# 03_LCD-Other.net
KiCad netlist of a schematic drawn in Altium Designer
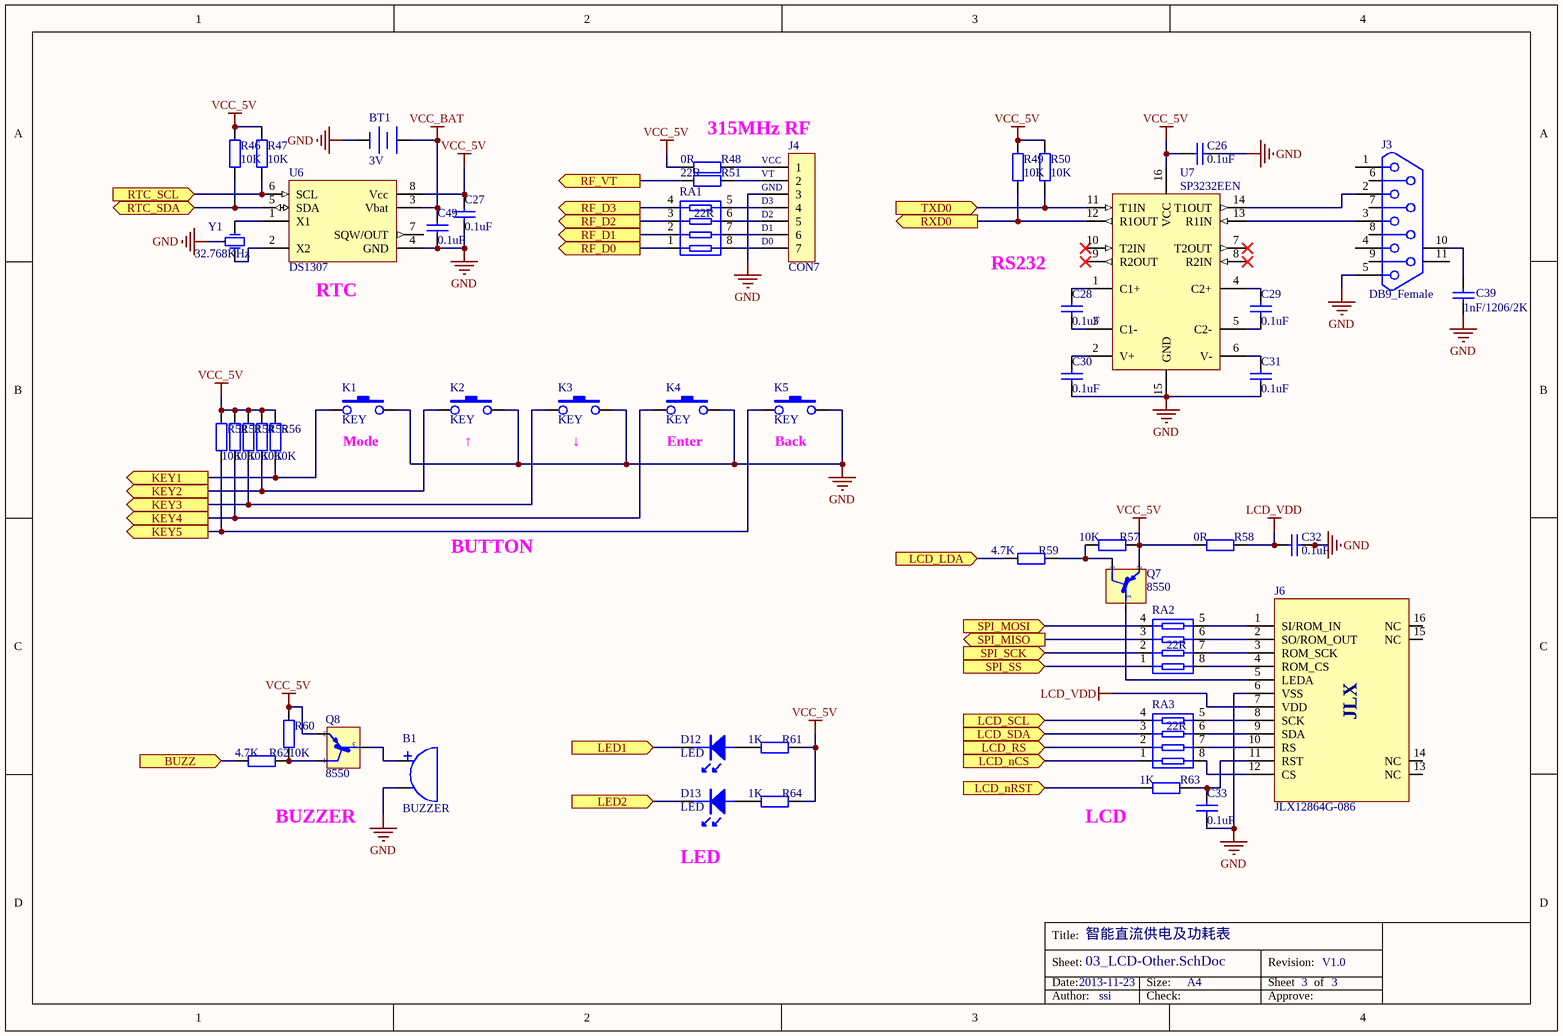
[diagram p0: 03_LCD-Other.SchDoc]

(export (version "E")
  (design (tool "Eeschema 10.0.6"))
  (components
    (comp (ref "B1")
      (value "BUZZER")
      (footprint "BUZZ")
      (description "Buzzer")
      (libsource (lib "SSD-Schlib1") (part "BUZZER"))
    )
    (comp (ref "BT1")
      (value "3V")
      (footprint "BATTERY_Mi")
      (description "Multicell Battery")
      (fields (field (name "PUBLISHER") "Altium Limited"))
      (libsource (lib "SSD-Schlib1") (part "Battery"))
    )
    (comp (ref "C26")
      (value "0.1uF")
      (footprint "0603C")
      (description "Capacitor")
      (fields (field (name "PUBLISHER") "Altium Limited"))
      (libsource (lib "SSD_LibPkg") (part "Cap"))
    )
    (comp (ref "C27")
      (value "0.1uF")
      (footprint "0603C")
      (description "Capacitor")
      (fields (field (name "PUBLISHER") "Altium Limited"))
      (libsource (lib "SSD-Schlib1") (part "Cap"))
    )
    (comp (ref "C28")
      (value "0.1uF")
      (footprint "0603C")
      (description "Capacitor")
      (fields (field (name "PUBLISHER") "Altium Limited"))
      (libsource (lib "SSD-Schlib1") (part "Cap"))
    )
    (comp (ref "C29")
      (value "0.1uF")
      (footprint "0603C")
      (description "Capacitor")
      (fields (field (name "PUBLISHER") "Altium Limited"))
      (libsource (lib "SSD-Schlib1") (part "Cap"))
    )
    (comp (ref "C30")
      (value "0.1uF")
      (footprint "0603C")
      (description "Capacitor")
      (fields (field (name "PUBLISHER") "Altium Limited"))
      (libsource (lib "SSD-Schlib1") (part "Cap"))
    )
    (comp (ref "C31")
      (value "0.1uF")
      (footprint "0603C")
      (description "Capacitor")
      (fields (field (name "PUBLISHER") "Altium Limited"))
      (libsource (lib "SSD-Schlib1") (part "Cap"))
    )
    (comp (ref "C32")
      (value "0.1uF")
      (footprint "0603C")
      (description "Capacitor")
      (fields (field (name "PUBLISHER") "Altium Limited"))
      (libsource (lib "SSD_LibPkg") (part "Cap"))
    )
    (comp (ref "C33")
      (value "0.1uF")
      (footprint "0603C")
      (description "Capacitor")
      (fields (field (name "PUBLISHER") "Altium Limited"))
      (libsource (lib "SSD_LibPkg") (part "Cap"))
    )
    (comp (ref "C39")
      (value "1nF/1206/2K")
      (footprint "1206")
      (description "Capacitor")
      (fields (field (name "PUBLISHER") "Altium Limited"))
      (libsource (lib "SSD-Schlib1") (part "Cap"))
    )
    (comp (ref "C49")
      (value "0.1uF")
      (footprint "0603C")
      (description "Capacitor")
      (fields (field (name "PUBLISHER") "Altium Limited"))
      (libsource (lib "SSD_LibPkg") (part "Cap"))
    )
    (comp (ref "D12") (value "LED") (footprint "LED-3.5mm") (libsource (lib "SSD-Schlib1") (part "LED")))
    (comp (ref "D13") (value "LED") (footprint "LED-3.5mm") (libsource (lib "SSD-Schlib1") (part "LED")))
    (comp (ref "J3")
      (value "DB9_Female")
      (footprint "DB9_F")
      (description "DB9_Female 母")
      (libsource (lib "SSD-Schlib1") (part "DB9_F"))
    )
    (comp (ref "J4") (value "CON7") (footprint "SIP7") (libsource (lib "SSD-Schlib1") (part "CON7")))
    (comp (ref "J6")
      (value "JLX12864G-086")
      (footprint "JLX12864G-086")
      (description "LCD12864 mini,43.5x40.8mm")
      (libsource (lib "SSD_LibPkg") (part "JLX12864G-086"))
    )
    (comp (ref "K1") (value "KEY") (footprint "SW_AJ_6X6") (libsource (lib "SSD-Schlib1") (part "KEY1")))
    (comp (ref "K2") (value "KEY") (footprint "SW_AJ_6X6") (libsource (lib "SSD-Schlib1") (part "KEY1")))
    (comp (ref "K3") (value "KEY") (footprint "SW_AJ_6X6") (libsource (lib "SSD-Schlib1") (part "KEY1")))
    (comp (ref "K4") (value "KEY") (footprint "SW_AJ_6X6") (libsource (lib "SSD-Schlib1") (part "KEY1")))
    (comp (ref "K5") (value "KEY") (footprint "SW_AJ_6X6") (libsource (lib "SSD-Schlib1") (part "KEY1")))
    (comp (ref "Q7")
      (value "8550")
      (footprint "SSD-PCBLIB1:SOT-23")
      (description "PNP")
      (libsource (lib "") (part "PNP_T_1"))
    )
    (comp (ref "Q8")
      (value "8550")
      (footprint "SSD-PCBLIB1:SOT-23")
      (description "PNP")
      (libsource (lib "SSD-Schlib1") (part "PNP_T"))
    )
    (comp (ref "R46")
      (value "10K")
      (footprint "0603")
      (description "Resistor")
      (fields (field (name "PUBLISHER") "Altium Limited"))
      (libsource (lib "SSD_LibPkg") (part "Res2"))
    )
    (comp (ref "R47")
      (value "10K")
      (footprint "0603")
      (description "Resistor")
      (fields (field (name "PUBLISHER") "Altium Limited"))
      (libsource (lib "SSD_LibPkg") (part "Res2"))
    )
    (comp (ref "R48")
      (value "0R")
      (footprint "0603")
      (description "Resistor")
      (fields (field (name "PUBLISHER") "Altium Limited"))
      (libsource (lib "") (part "Res2_1"))
    )
    (comp (ref "R49")
      (value "10K")
      (footprint "0603")
      (description "Resistor")
      (fields (field (name "PUBLISHER") "Altium Limited"))
      (libsource (lib "SSD_LibPkg") (part "Res2"))
    )
    (comp (ref "R50")
      (value "10K")
      (footprint "0603")
      (description "Resistor")
      (fields (field (name "PUBLISHER") "Altium Limited"))
      (libsource (lib "SSD_LibPkg") (part "Res2"))
    )
    (comp (ref "R51")
      (value "22R")
      (footprint "0603")
      (description "Resistor")
      (fields (field (name "PUBLISHER") "Altium Limited"))
      (libsource (lib "") (part "Res2_1"))
    )
    (comp (ref "R52")
      (value "10K")
      (footprint "0603")
      (description "Resistor")
      (fields (field (name "PUBLISHER") "Altium Limited"))
      (libsource (lib "SSD-Schlib1") (part "Res2"))
    )
    (comp (ref "R53")
      (value "10K")
      (footprint "0603")
      (description "Resistor")
      (fields (field (name "PUBLISHER") "Altium Limited"))
      (libsource (lib "SSD-Schlib1") (part "Res2"))
    )
    (comp (ref "R54")
      (value "10K")
      (footprint "0603")
      (description "Resistor")
      (fields (field (name "PUBLISHER") "Altium Limited"))
      (libsource (lib "SSD-Schlib1") (part "Res2"))
    )
    (comp (ref "R55")
      (value "10K")
      (footprint "0603")
      (description "Resistor")
      (fields (field (name "PUBLISHER") "Altium Limited"))
      (libsource (lib "SSD-Schlib1") (part "Res2"))
    )
    (comp (ref "R56")
      (value "10K")
      (footprint "0603")
      (description "Resistor")
      (fields (field (name "PUBLISHER") "Altium Limited"))
      (libsource (lib "SSD-Schlib1") (part "Res2"))
    )
    (comp (ref "R57")
      (value "10K")
      (footprint "0603")
      (description "Resistor")
      (fields (field (name "PUBLISHER") "Altium Limited"))
      (libsource (lib "") (part "Res2_1"))
    )
    (comp (ref "R58")
      (value "0R")
      (footprint "0603")
      (description "Resistor")
      (fields (field (name "PUBLISHER") "Altium Limited"))
      (libsource (lib "") (part "Res2_1"))
    )
    (comp (ref "R59")
      (value "4.7K")
      (footprint "0603")
      (description "Resistor")
      (fields (field (name "PUBLISHER") "Altium Limited"))
      (libsource (lib "") (part "Res2_1"))
    )
    (comp (ref "R60")
      (value "10K")
      (footprint "0603")
      (description "Resistor")
      (fields (field (name "PUBLISHER") "Altium Limited"))
      (libsource (lib "SSD-Schlib1") (part "Res2"))
    )
    (comp (ref "R61")
      (value "1K")
      (footprint "0603")
      (description "Resistor")
      (fields (field (name "PUBLISHER") "Altium Limited"))
      (libsource (lib "") (part "Res2_1"))
    )
    (comp (ref "R62")
      (value "4.7K")
      (footprint "0603")
      (description "Resistor")
      (fields (field (name "PUBLISHER") "Altium Limited"))
      (libsource (lib "") (part "Res2_1"))
    )
    (comp (ref "R63")
      (value "1K")
      (footprint "0603")
      (description "Resistor")
      (fields (field (name "PUBLISHER") "Altium Limited"))
      (libsource (lib "") (part "Res2_1"))
    )
    (comp (ref "R64")
      (value "1K")
      (footprint "0603")
      (description "Resistor")
      (fields (field (name "PUBLISHER") "Altium Limited"))
      (libsource (lib "") (part "Res2_1"))
    )
    (comp (ref "RA1")
      (value "22R")
      (footprint "0603x4")
      (description "Isolated Resistor Network")
      (libsource (lib "SSD_LibPkg") (part "Res x4"))
    )
    (comp (ref "RA2")
      (value "22R")
      (footprint "0603x4")
      (description "Isolated Resistor Network")
      (libsource (lib "SSD_LibPkg") (part "Res x4"))
    )
    (comp (ref "RA3")
      (value "22R")
      (footprint "0603x4")
      (description "Isolated Resistor Network")
      (libsource (lib "SSD_LibPkg") (part "Res x4"))
    )
    (comp (ref "U6") (value "DS1307") (footprint "SO-8") (libsource (lib "SSD-Schlib1") (part "DS1307")))
    (comp (ref "U7")
      (value "SP3232EEN")
      (footprint "SO16")
      (description "3  to 5V Powered, Multi-Channel RS-232 Driver/Receiver")
      (fields (field (name "PUBLISHER") "Altium Limited"))
      (libsource (lib "SSD-Schlib1") (part "SP3232"))
    )
    (comp (ref "Y1")
      (value "32.768KHz")
      (footprint "XTAL-32K-B")
      (description "Crystal Oscillator")
      (fields (field (name "PUBLISHER") "Altium Limited"))
      (libsource (lib "SSD-Schlib1") (part "XTAL32-3"))
    )
  )
  (nets
    (net (code "1") (name "/BUZZ") (class "Default")
      (node (ref "R62") (pin "1") (pinfunction "1_1") (pintype "passive"))
    )
    (net (code "2") (name "/KEY1") (class "Default")
      (node (ref "K1") (pin "1") (pinfunction "1_1") (pintype "passive"))
      (node (ref "R56") (pin "1") (pinfunction "1_1") (pintype "passive"))
    )
    (net (code "3") (name "/KEY2") (class "Default")
      (node (ref "K2") (pin "1") (pinfunction "1_1") (pintype "passive"))
      (node (ref "R55") (pin "1") (pinfunction "1_1") (pintype "passive"))
    )
    (net (code "4") (name "/KEY3") (class "Default")
      (node (ref "K3") (pin "1") (pinfunction "1_1") (pintype "passive"))
      (node (ref "R54") (pin "1") (pinfunction "1_1") (pintype "passive"))
    )
    (net (code "5") (name "/KEY4") (class "Default")
      (node (ref "K4") (pin "1") (pinfunction "1_1") (pintype "passive"))
      (node (ref "R53") (pin "1") (pinfunction "1_1") (pintype "passive"))
    )
    (net (code "6") (name "/KEY5") (class "Default")
      (node (ref "K5") (pin "1") (pinfunction "1_1") (pintype "passive"))
      (node (ref "R52") (pin "1") (pinfunction "1_1") (pintype "passive"))
    )
    (net (code "7") (name "/LCD_LDA") (class "Default")
      (node (ref "R59") (pin "2") (pinfunction "2_2") (pintype "passive"))
    )
    (net (code "8") (name "/LCD_RS") (class "Default")
      (node (ref "RA3") (pin "2") (pinfunction "2_2") (pintype "passive"))
    )
    (net (code "9") (name "/LCD_SCL") (class "Default")
      (node (ref "RA3") (pin "4") (pinfunction "4_4") (pintype "passive"))
    )
    (net (code "10") (name "/LCD_SDA") (class "Default")
      (node (ref "RA3") (pin "3") (pinfunction "3_3") (pintype "passive"))
    )
    (net (code "11") (name "/LCD_nCS") (class "Default")
      (node (ref "RA3") (pin "1") (pinfunction "1_1") (pintype "passive"))
    )
    (net (code "12") (name "/LCD_nRST") (class "Default")
      (node (ref "R63") (pin "2") (pinfunction "2_2") (pintype "passive"))
    )
    (net (code "13") (name "/LED1") (class "Default")
      (node (ref "D12") (pin "2") (pinfunction "K_2") (pintype "passive"))
    )
    (net (code "14") (name "/LED2") (class "Default")
      (node (ref "D13") (pin "2") (pinfunction "K_2") (pintype "passive"))
    )
    (net (code "15") (name "/RF_D0") (class "Default")
      (node (ref "RA1") (pin "1") (pinfunction "1_1") (pintype "passive"))
    )
    (net (code "16") (name "/RF_D1") (class "Default")
      (node (ref "RA1") (pin "2") (pinfunction "2_2") (pintype "passive"))
    )
    (net (code "17") (name "/RF_D2") (class "Default")
      (node (ref "RA1") (pin "3") (pinfunction "3_3") (pintype "passive"))
    )
    (net (code "18") (name "/RF_D3") (class "Default")
      (node (ref "RA1") (pin "4") (pinfunction "4_4") (pintype "passive"))
    )
    (net (code "19") (name "/RF_VT") (class "Default")
      (node (ref "R51") (pin "2") (pinfunction "2_2") (pintype "passive"))
    )
    (net (code "20") (name "/RTC_SCL") (class "Default")
      (node (ref "R47") (pin "2") (pinfunction "2_2") (pintype "passive"))
      (node (ref "U6") (pin "6") (pinfunction "SCL_6") (pintype "input"))
    )
    (net (code "21") (name "/RTC_SDA") (class "Default")
      (node (ref "R46") (pin "2") (pinfunction "2_2") (pintype "passive"))
      (node (ref "U6") (pin "5") (pinfunction "SDA_5") (pintype "bidirectional"))
    )
    (net (code "22") (name "/RXD0") (class "Default")
      (node (ref "R49") (pin "2") (pinfunction "2_2") (pintype "passive"))
      (node (ref "U7") (pin "12") (pinfunction "R1OUT_12") (pintype "output"))
    )
    (net (code "23") (name "/SPI_MISO") (class "Default")
      (node (ref "RA2") (pin "3") (pinfunction "3_3") (pintype "passive"))
    )
    (net (code "24") (name "/SPI_MOSI") (class "Default")
      (node (ref "RA2") (pin "4") (pinfunction "4_4") (pintype "passive"))
    )
    (net (code "25") (name "/SPI_SCK") (class "Default")
      (node (ref "RA2") (pin "2") (pinfunction "2_2") (pintype "passive"))
    )
    (net (code "26") (name "/SPI_SS") (class "Default")
      (node (ref "RA2") (pin "1") (pinfunction "1_1") (pintype "passive"))
    )
    (net (code "27") (name "/TXD0") (class "Default")
      (node (ref "R50") (pin "2") (pinfunction "2_2") (pintype "passive"))
      (node (ref "U7") (pin "11") (pinfunction "T1IN_11") (pintype "input"))
    )
    (net (code "28") (name "GND") (class "Default")
      (node (ref "B1") (pin "2") (pinfunction "B_2") (pintype "passive"))
      (node (ref "BT1") (pin "2") (pinfunction "-_2") (pintype "passive"))
      (node (ref "C26") (pin "1") (pinfunction "1_1") (pintype "passive"))
      (node (ref "C27") (pin "1") (pinfunction "1_1") (pintype "passive"))
      (node (ref "C30") (pin "1") (pinfunction "1_1") (pintype "passive"))
      (node (ref "C31") (pin "1") (pinfunction "1_1") (pintype "passive"))
      (node (ref "C32") (pin "1") (pinfunction "1_1") (pintype "passive"))
      (node (ref "C33") (pin "1") (pinfunction "1_1") (pintype "passive"))
      (node (ref "C39") (pin "1") (pinfunction "1_1") (pintype "passive"))
      (node (ref "C49") (pin "2") (pinfunction "2_2") (pintype "passive"))
      (node (ref "J3") (pin "5") (pinfunction "5_5") (pintype "passive"))
      (node (ref "J4") (pin "3") (pinfunction "3_3") (pintype "passive"))
      (node (ref "J6") (pin "6") (pinfunction "VSS_6") (pintype "passive"))
      (node (ref "K1") (pin "2") (pinfunction "2_2") (pintype "passive"))
      (node (ref "K2") (pin "2") (pinfunction "2_2") (pintype "passive"))
      (node (ref "K3") (pin "2") (pinfunction "2_2") (pintype "passive"))
      (node (ref "K4") (pin "2") (pinfunction "2_2") (pintype "passive"))
      (node (ref "K5") (pin "2") (pinfunction "2_2") (pintype "passive"))
      (node (ref "U6") (pin "4") (pinfunction "GND_4") (pintype "power_in"))
      (node (ref "U7") (pin "15") (pinfunction "GND_15") (pintype "power_in"))
      (node (ref "Y1") (pin "3") (pinfunction "3_3") (pintype "passive"))
    )
    (net (code "29") (name "LCD_VDD") (class "Default")
      (node (ref "C32") (pin "2") (pinfunction "2_2") (pintype "passive"))
      (node (ref "J6") (pin "7") (pinfunction "VDD_7") (pintype "passive"))
      (node (ref "R58") (pin "1") (pinfunction "1_1") (pintype "passive"))
    )
    (net (code "30") (name "Net-(B1-A)") (class "Default")
      (node (ref "B1") (pin "1") (pinfunction "A_1") (pintype "passive"))
      (node (ref "Q8") (pin "3") (pinfunction "C_3") (pintype "passive"))
    )
    (net (code "31") (name "Net-(C39-Pad2)") (class "Default")
      (node (ref "C39") (pin "2") (pinfunction "2_2") (pintype "passive"))
      (node (ref "J3") (pin "10") (pinfunction "10_10") (pintype "passive"))
    )
    (net (code "32") (name "Net-(D12-A)") (class "Default")
      (node (ref "D12") (pin "1") (pinfunction "A_1") (pintype "passive"))
      (node (ref "R61") (pin "1") (pinfunction "1_1") (pintype "passive"))
    )
    (net (code "33") (name "Net-(D13-A)") (class "Default")
      (node (ref "D13") (pin "1") (pinfunction "A_1") (pintype "passive"))
      (node (ref "R64") (pin "1") (pinfunction "1_1") (pintype "passive"))
    )
    (net (code "34") (name "Net-(J4-Pad1)") (class "Default")
      (node (ref "J4") (pin "1") (pinfunction "1_1") (pintype "passive"))
      (node (ref "R48") (pin "1") (pinfunction "1_1") (pintype "passive"))
    )
    (net (code "35") (name "Net-(J4-Pad2)") (class "Default")
      (node (ref "J4") (pin "2") (pinfunction "2_2") (pintype "passive"))
      (node (ref "R51") (pin "1") (pinfunction "1_1") (pintype "passive"))
    )
    (net (code "36") (name "Net-(J4-Pad4)") (class "Default")
      (node (ref "J4") (pin "4") (pinfunction "4_4") (pintype "passive"))
      (node (ref "RA1") (pin "5") (pinfunction "5_5") (pintype "passive"))
    )
    (net (code "37") (name "Net-(J4-Pad5)") (class "Default")
      (node (ref "J4") (pin "5") (pinfunction "5_5") (pintype "passive"))
      (node (ref "RA1") (pin "6") (pinfunction "6_6") (pintype "passive"))
    )
    (net (code "38") (name "Net-(J4-Pad6)") (class "Default")
      (node (ref "J4") (pin "6") (pinfunction "6_6") (pintype "passive"))
      (node (ref "RA1") (pin "7") (pinfunction "7_7") (pintype "passive"))
    )
    (net (code "39") (name "Net-(J4-Pad7)") (class "Default")
      (node (ref "J4") (pin "7") (pinfunction "7_7") (pintype "passive"))
      (node (ref "RA1") (pin "8") (pinfunction "8_8") (pintype "passive"))
    )
    (net (code "40") (name "Net-(J6-CS)") (class "Default")
      (node (ref "J6") (pin "12") (pinfunction "CS_12") (pintype "passive"))
      (node (ref "RA3") (pin "8") (pinfunction "8_8") (pintype "passive"))
    )
    (net (code "41") (name "Net-(J6-LEDA)") (class "Default")
      (node (ref "J6") (pin "5") (pinfunction "LEDA_5") (pintype "passive"))
      (node (ref "Q7") (pin "3") (pinfunction "C_3") (pintype "passive"))
    )
    (net (code "42") (name "Net-(J6-ROM_CS)") (class "Default")
      (node (ref "J6") (pin "4") (pinfunction "ROM_CS_4") (pintype "passive"))
      (node (ref "RA2") (pin "8") (pinfunction "8_8") (pintype "passive"))
    )
    (net (code "43") (name "Net-(J6-ROM_SCK)") (class "Default")
      (node (ref "J6") (pin "3") (pinfunction "ROM_SCK_3") (pintype "passive"))
      (node (ref "RA2") (pin "7") (pinfunction "7_7") (pintype "passive"))
    )
    (net (code "44") (name "Net-(J6-RS)") (class "Default")
      (node (ref "J6") (pin "10") (pinfunction "RS_10") (pintype "passive"))
      (node (ref "RA3") (pin "7") (pinfunction "7_7") (pintype "passive"))
    )
    (net (code "45") (name "Net-(J6-RST)") (class "Default")
      (node (ref "C33") (pin "2") (pinfunction "2_2") (pintype "passive"))
      (node (ref "J6") (pin "11") (pinfunction "RST_11") (pintype "passive"))
      (node (ref "R63") (pin "1") (pinfunction "1_1") (pintype "passive"))
    )
    (net (code "46") (name "Net-(J6-SCK)") (class "Default")
      (node (ref "J6") (pin "8") (pinfunction "SCK_8") (pintype "passive"))
      (node (ref "RA3") (pin "5") (pinfunction "5_5") (pintype "passive"))
    )
    (net (code "47") (name "Net-(J6-SDA)") (class "Default")
      (node (ref "J6") (pin "9") (pinfunction "SDA_9") (pintype "passive"))
      (node (ref "RA3") (pin "6") (pinfunction "6_6") (pintype "passive"))
    )
    (net (code "48") (name "Net-(J6-SI{slash}ROM_IN)") (class "Default")
      (node (ref "J6") (pin "1") (pinfunction "SI/ROM_IN_1") (pintype "passive"))
      (node (ref "RA2") (pin "5") (pinfunction "5_5") (pintype "passive"))
    )
    (net (code "49") (name "Net-(J6-SO{slash}ROM_OUT)") (class "Default")
      (node (ref "J6") (pin "2") (pinfunction "SO/ROM_OUT_2") (pintype "passive"))
      (node (ref "RA2") (pin "6") (pinfunction "6_6") (pintype "passive"))
    )
    (net (code "50") (name "Net-(Q7-B)") (class "Default")
      (node (ref "Q7") (pin "1") (pinfunction "B_1") (pintype "passive"))
      (node (ref "R57") (pin "2") (pinfunction "2_2") (pintype "passive"))
      (node (ref "R59") (pin "1") (pinfunction "1_1") (pintype "passive"))
    )
    (net (code "51") (name "Net-(Q8-B)") (class "Default")
      (node (ref "Q8") (pin "1") (pinfunction "B_1") (pintype "passive"))
      (node (ref "R60") (pin "1") (pinfunction "1_1") (pintype "passive"))
      (node (ref "R62") (pin "2") (pinfunction "2_2") (pintype "passive"))
    )
    (net (code "52") (name "Net-(U6-X1)") (class "Default")
      (node (ref "U6") (pin "1") (pinfunction "X1_1") (pintype "passive"))
      (node (ref "Y1") (pin "2") (pinfunction "OSC2_2") (pintype "passive"))
    )
    (net (code "53") (name "Net-(U6-X2)") (class "Default")
      (node (ref "U6") (pin "2") (pinfunction "X2_2") (pintype "passive"))
      (node (ref "Y1") (pin "1") (pinfunction "OSC1_1") (pintype "passive"))
    )
    (net (code "54") (name "Net-(U7-C1+)") (class "Default")
      (node (ref "C28") (pin "2") (pinfunction "2_2") (pintype "passive"))
      (node (ref "U7") (pin "1") (pinfunction "C1+_1") (pintype "passive"))
    )
    (net (code "55") (name "Net-(U7-C1-)") (class "Default")
      (node (ref "C28") (pin "1") (pinfunction "1_1") (pintype "passive"))
      (node (ref "U7") (pin "3") (pinfunction "C1-_3") (pintype "passive"))
    )
    (net (code "56") (name "Net-(U7-C2+)") (class "Default")
      (node (ref "C29") (pin "2") (pinfunction "2_2") (pintype "passive"))
      (node (ref "U7") (pin "4") (pinfunction "C2+_4") (pintype "passive"))
    )
    (net (code "57") (name "Net-(U7-C2-)") (class "Default")
      (node (ref "C29") (pin "1") (pinfunction "1_1") (pintype "passive"))
      (node (ref "U7") (pin "5") (pinfunction "C2-_5") (pintype "passive"))
    )
    (net (code "58") (name "Net-(U7-R1IN)") (class "Default")
      (node (ref "J3") (pin "3") (pinfunction "3_3") (pintype "passive"))
      (node (ref "U7") (pin "13") (pinfunction "R1IN_13") (pintype "input"))
    )
    (net (code "59") (name "Net-(U7-T1OUT)") (class "Default")
      (node (ref "J3") (pin "2") (pinfunction "2_2") (pintype "passive"))
      (node (ref "U7") (pin "14") (pinfunction "T1OUT_14") (pintype "output"))
    )
    (net (code "60") (name "Net-(U7-V+)") (class "Default")
      (node (ref "C30") (pin "2") (pinfunction "2_2") (pintype "passive"))
      (node (ref "U7") (pin "2") (pinfunction "V+_2") (pintype "power_in"))
    )
    (net (code "61") (name "Net-(U7-V-)") (class "Default")
      (node (ref "C31") (pin "2") (pinfunction "2_2") (pintype "passive"))
      (node (ref "U7") (pin "6") (pinfunction "V-_6") (pintype "power_in"))
    )
    (net (code "62") (name "VCC_5V") (class "Default")
      (node (ref "C26") (pin "2") (pinfunction "2_2") (pintype "passive"))
      (node (ref "C27") (pin "2") (pinfunction "2_2") (pintype "passive"))
      (node (ref "Q7") (pin "2") (pinfunction "E_2") (pintype "passive"))
      (node (ref "Q8") (pin "2") (pinfunction "E_2") (pintype "passive"))
      (node (ref "R46") (pin "1") (pinfunction "1_1") (pintype "passive"))
      (node (ref "R47") (pin "1") (pinfunction "1_1") (pintype "passive"))
      (node (ref "R48") (pin "2") (pinfunction "2_2") (pintype "passive"))
      (node (ref "R49") (pin "1") (pinfunction "1_1") (pintype "passive"))
      (node (ref "R50") (pin "1") (pinfunction "1_1") (pintype "passive"))
      (node (ref "R52") (pin "2") (pinfunction "2_2") (pintype "passive"))
      (node (ref "R53") (pin "2") (pinfunction "2_2") (pintype "passive"))
      (node (ref "R54") (pin "2") (pinfunction "2_2") (pintype "passive"))
      (node (ref "R55") (pin "2") (pinfunction "2_2") (pintype "passive"))
      (node (ref "R56") (pin "2") (pinfunction "2_2") (pintype "passive"))
      (node (ref "R57") (pin "1") (pinfunction "1_1") (pintype "passive"))
      (node (ref "R58") (pin "2") (pinfunction "2_2") (pintype "passive"))
      (node (ref "R60") (pin "2") (pinfunction "2_2") (pintype "passive"))
      (node (ref "R61") (pin "2") (pinfunction "2_2") (pintype "passive"))
      (node (ref "R64") (pin "2") (pinfunction "2_2") (pintype "passive"))
      (node (ref "U6") (pin "8") (pinfunction "Vcc_8") (pintype "power_in"))
      (node (ref "U7") (pin "16") (pinfunction "VCC_16") (pintype "power_in"))
    )
    (net (code "63") (name "VCC_BAT") (class "Default")
      (node (ref "BT1") (pin "1") (pinfunction "+_1") (pintype "passive"))
      (node (ref "C49") (pin "1") (pinfunction "1_1") (pintype "passive"))
      (node (ref "U6") (pin "3") (pinfunction "Vbat_3") (pintype "power_in"))
    )
    (net (code "64") (name "unconnected-(J3-Pad1)") (class "Default")
      (node (ref "J3") (pin "1") (pinfunction "1_1") (pintype "passive"))
    )
    (net (code "65") (name "unconnected-(J3-Pad4)") (class "Default")
      (node (ref "J3") (pin "4") (pinfunction "4_4") (pintype "passive"))
    )
    (net (code "66") (name "unconnected-(J3-Pad6)") (class "Default")
      (node (ref "J3") (pin "6") (pinfunction "6_6") (pintype "passive"))
    )
    (net (code "67") (name "unconnected-(J3-Pad7)") (class "Default")
      (node (ref "J3") (pin "7") (pinfunction "7_7") (pintype "passive"))
    )
    (net (code "68") (name "unconnected-(J3-Pad8)") (class "Default")
      (node (ref "J3") (pin "8") (pinfunction "8_8") (pintype "passive"))
    )
    (net (code "69") (name "unconnected-(J3-Pad9)") (class "Default")
      (node (ref "J3") (pin "9") (pinfunction "9_9") (pintype "passive"))
    )
    (net (code "70") (name "unconnected-(J3-Pad11)") (class "Default")
      (node (ref "J3") (pin "11") (pinfunction "11_11") (pintype "passive"))
    )
    (net (code "71") (name "unconnected-(J6-NC-Pad13)") (class "Default")
      (node (ref "J6") (pin "13") (pinfunction "NC_13") (pintype "passive"))
    )
    (net (code "72") (name "unconnected-(J6-NC-Pad14)") (class "Default")
      (node (ref "J6") (pin "14") (pinfunction "NC_14") (pintype "passive"))
    )
    (net (code "73") (name "unconnected-(J6-NC-Pad15)") (class "Default")
      (node (ref "J6") (pin "15") (pinfunction "NC_15") (pintype "passive"))
    )
    (net (code "74") (name "unconnected-(J6-NC-Pad16)") (class "Default")
      (node (ref "J6") (pin "16") (pinfunction "NC_16") (pintype "passive"))
    )
    (net (code "75") (name "unconnected-(U6-SQW{slash}OUT-Pad7)") (class "Default")
      (node (ref "U6") (pin "7") (pinfunction "SQW/OUT_7") (pintype "output"))
    )
    (net (code "76") (name "unconnected-(U7-R2IN-Pad8)") (class "Default")
      (node (ref "U7") (pin "8") (pinfunction "R2IN_8") (pintype "input+no_connect"))
    )
    (net (code "77") (name "unconnected-(U7-R2OUT-Pad9)") (class "Default")
      (node (ref "U7") (pin "9") (pinfunction "R2OUT_9") (pintype "output+no_connect"))
    )
    (net (code "78") (name "unconnected-(U7-T2IN-Pad10)") (class "Default")
      (node (ref "U7") (pin "10") (pinfunction "T2IN_10") (pintype "input+no_connect"))
    )
    (net (code "79") (name "unconnected-(U7-T2OUT-Pad7)") (class "Default")
      (node (ref "U7") (pin "7") (pinfunction "T2OUT_7") (pintype "output+no_connect"))
    )
  )
)
